# BPC_Clock.net
KiCad netlist of a schematic drawn in Altium Designer
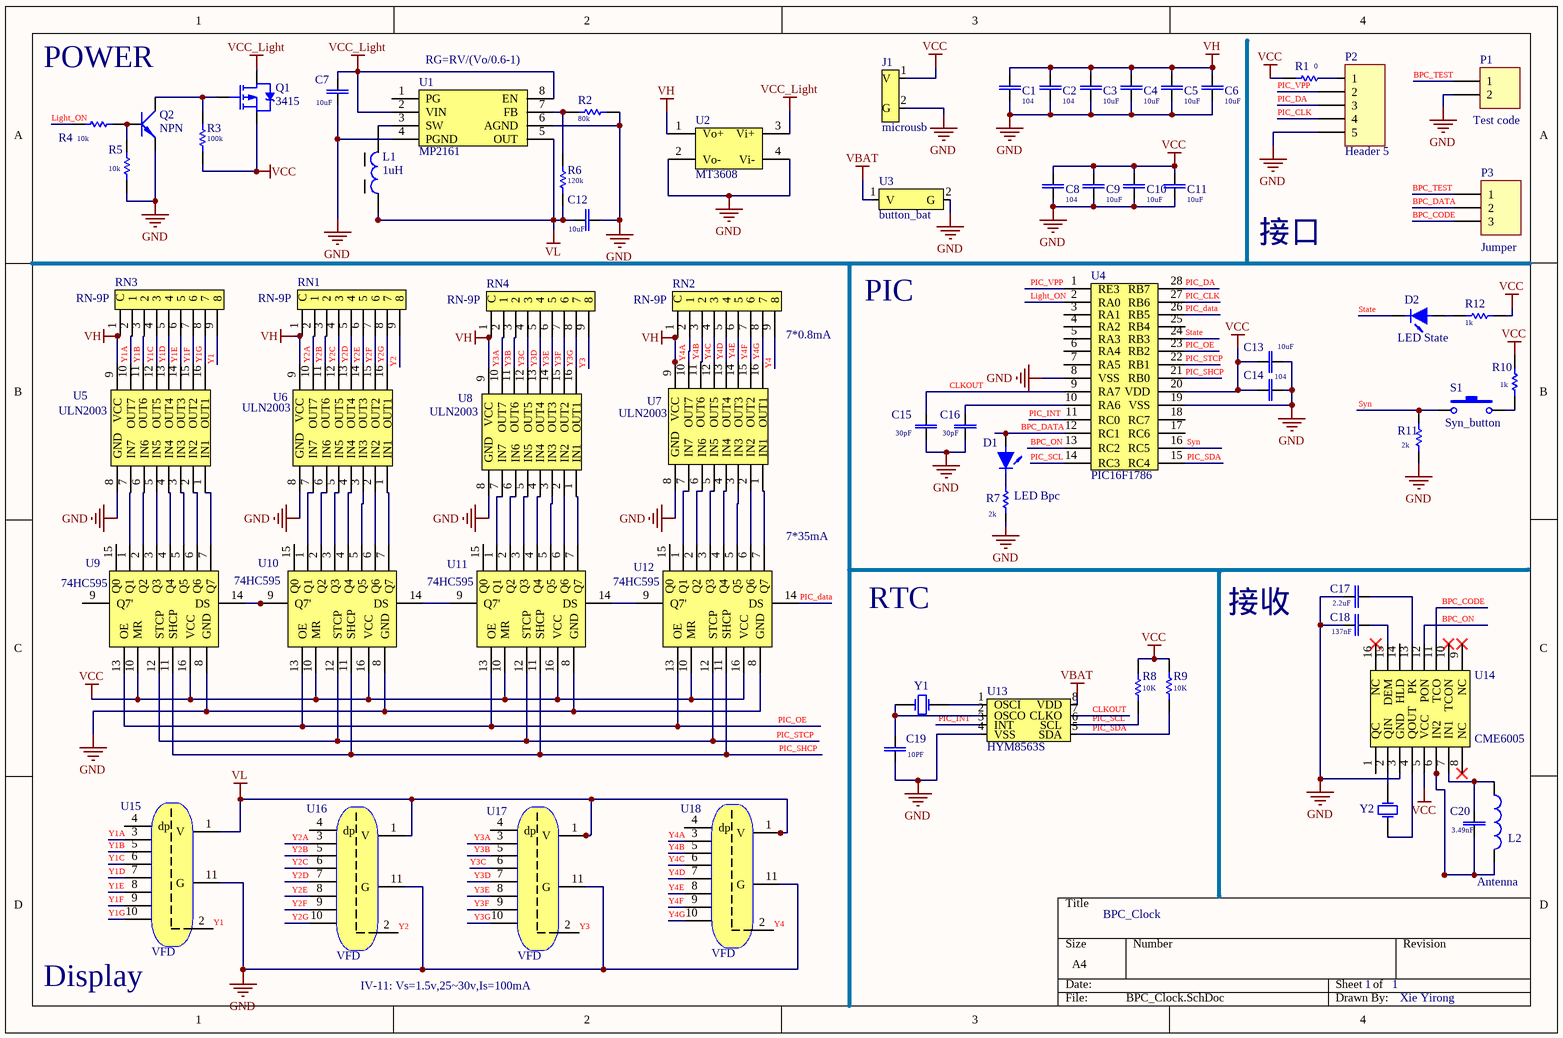
[diagram p0: BPC_Clock.SchDoc]

(export (version "E")
  (design (tool "Eeschema 10.0.6"))
  (components
    (comp (ref "C1")
      (value "104")
      (footprint "CAPC2012N")
      (description "Capacitor")
      (fields (field (name "Comment") "Cap") (field (name "PUBLISHER") "Altium Limited"))
      (libsource (lib "Miscellaneous Devices") (part "Cap"))
    )
    (comp (ref "C2")
      (value "104")
      (footprint "CAPC2012N")
      (description "Capacitor")
      (fields (field (name "Comment") "Cap") (field (name "PUBLISHER") "Altium Limited"))
      (libsource (lib "Miscellaneous Devices") (part "Cap"))
    )
    (comp (ref "C3")
      (value "10uF")
      (footprint "CAPC2012N")
      (description "Capacitor")
      (fields (field (name "Comment") "Cap") (field (name "PUBLISHER") "Altium Limited"))
      (libsource (lib "Miscellaneous Devices") (part "Cap"))
    )
    (comp (ref "C4")
      (value "10uF")
      (footprint "CAPC2012N")
      (description "Capacitor")
      (fields (field (name "Comment") "Cap") (field (name "PUBLISHER") "Altium Limited"))
      (libsource (lib "Miscellaneous Devices") (part "Cap"))
    )
    (comp (ref "C5")
      (value "10uF")
      (footprint "CAPC2012N")
      (description "Capacitor")
      (fields (field (name "Comment") "Cap") (field (name "PUBLISHER") "Altium Limited"))
      (libsource (lib "Miscellaneous Devices") (part "Cap"))
    )
    (comp (ref "C6")
      (value "10uF")
      (footprint "CAPC2012N")
      (description "Capacitor")
      (fields (field (name "Comment") "Cap") (field (name "PUBLISHER") "Altium Limited"))
      (libsource (lib "Miscellaneous Devices") (part "Cap"))
    )
    (comp (ref "C7")
      (value "10uF")
      (footprint "CAPC2012N")
      (description "Capacitor")
      (fields (field (name "Comment") "Cap") (field (name "PUBLISHER") "Altium Limited"))
      (libsource (lib "Miscellaneous Devices") (part "Cap"))
    )
    (comp (ref "C8")
      (value "104")
      (footprint "CAPC2012N")
      (description "Capacitor")
      (fields (field (name "Comment") "Cap") (field (name "PUBLISHER") "Altium Limited"))
      (libsource (lib "Miscellaneous Devices") (part "Cap"))
    )
    (comp (ref "C9")
      (value "10uF")
      (footprint "CAPC2012N")
      (description "Capacitor")
      (fields (field (name "Comment") "Cap") (field (name "PUBLISHER") "Altium Limited"))
      (libsource (lib "Miscellaneous Devices") (part "Cap"))
    )
    (comp (ref "C10")
      (value "10uF")
      (footprint "CAPC2012N")
      (description "Capacitor")
      (fields (field (name "Comment") "Cap") (field (name "PUBLISHER") "Altium Limited"))
      (libsource (lib "Miscellaneous Devices") (part "Cap"))
    )
    (comp (ref "C11")
      (value "10uF")
      (footprint "CAPC2012N")
      (description "Capacitor")
      (fields (field (name "Comment") "Cap") (field (name "PUBLISHER") "Altium Limited"))
      (libsource (lib "Miscellaneous Devices") (part "Cap"))
    )
    (comp (ref "C12")
      (value "10uF")
      (footprint "CAPC2012N")
      (description "Capacitor")
      (fields (field (name "Comment") "Cap") (field (name "PUBLISHER") "Altium Limited"))
      (libsource (lib "Miscellaneous Devices") (part "Cap"))
    )
    (comp (ref "C13")
      (value "10uF")
      (footprint "CAPC2012N")
      (description "Capacitor")
      (fields (field (name "Comment") "Cap") (field (name "PUBLISHER") "Altium Limited"))
      (libsource (lib "Miscellaneous Devices") (part "Cap"))
    )
    (comp (ref "C14")
      (value "104")
      (footprint "CAPC2012N")
      (description "Capacitor")
      (fields (field (name "Comment") "Cap") (field (name "PUBLISHER") "Altium Limited"))
      (libsource (lib "Miscellaneous Devices") (part "Cap"))
    )
    (comp (ref "C15")
      (value "30pF")
      (footprint "CAPC2012N")
      (description "Capacitor")
      (fields (field (name "Comment") "Cap") (field (name "PUBLISHER") "Altium Limited"))
      (libsource (lib "Miscellaneous Devices") (part "Cap"))
    )
    (comp (ref "C16")
      (value "30pF")
      (footprint "CAPC2012N")
      (description "Capacitor")
      (fields (field (name "Comment") "Cap") (field (name "PUBLISHER") "Altium Limited"))
      (libsource (lib "Miscellaneous Devices") (part "Cap"))
    )
    (comp (ref "C17")
      (value "2.2uF")
      (footprint "CAPC2012N")
      (description "Capacitor")
      (fields (field (name "Comment") "Cap") (field (name "PUBLISHER") "Altium Limited"))
      (libsource (lib "Miscellaneous Devices") (part "Cap"))
    )
    (comp (ref "C18")
      (value "137nF")
      (footprint "CAPC2012N")
      (description "Capacitor")
      (fields (field (name "Comment") "Cap") (field (name "PUBLISHER") "Altium Limited"))
      (libsource (lib "Miscellaneous Devices") (part "Cap"))
    )
    (comp (ref "C19")
      (value "10PF")
      (footprint "CAPC2012N")
      (description "Capacitor")
      (fields (field (name "Comment") "Cap") (field (name "PUBLISHER") "Altium Limited"))
      (libsource (lib "Miscellaneous Devices") (part "Cap"))
    )
    (comp (ref "C20")
      (value "3.49nF")
      (footprint "CAPC2012N")
      (description "Capacitor")
      (fields (field (name "Comment") "Cap") (field (name "PUBLISHER") "Altium Limited"))
      (libsource (lib "Miscellaneous Devices") (part "Cap"))
    )
    (comp (ref "D1")
      (value "LED Bpc")
      (footprint "CAPC2512N")
      (description "Typical RED, GREEN, YELLOW, AMBER GaAs LED")
      (fields (field (name "PUBLISHER") "Altium Limited"))
      (libsource (lib "Miscellaneous Devices") (part "LED2"))
    )
    (comp (ref "D2")
      (value "LED State")
      (footprint "CAPC2512N")
      (description "Typical RED, GREEN, YELLOW, AMBER GaAs LED")
      (fields (field (name "PUBLISHER") "Altium Limited"))
      (libsource (lib "Miscellaneous Devices") (part "LED2"))
    )
    (comp (ref "J1") (value "microusb") (footprint "microusb") (libsource (lib "microusb") (part "microusb")))
    (comp (ref "L1")
      (value "Chip inductors")
      (footprint "PCBComponent_1")
      (fields (field (name "ALTIUM_UNNAMED_1") "1uH"))
      (libsource (lib "Chip inductors") (part "Chip inductors"))
    )
    (comp (ref "L2")
      (value "Antenna")
      (footprint "CAPC2012N")
      (description "Inductor")
      (fields (field (name "PUBLISHER") "Altium Limited"))
      (libsource (lib "Miscellaneous Devices") (part "Inductor"))
    )
    (comp (ref "P1")
      (value "Test code")
      (footprint "HDR1X2")
      (description "Header, 2-Pin")
      (fields (field (name "PUBLISHER") "Altium Limited"))
      (libsource (lib "Miscellaneous Connectors") (part "Header 2"))
    )
    (comp (ref "P2")
      (value "Header 5")
      (footprint "HDR1X5")
      (description "Header, 5-Pin")
      (fields (field (name "PUBLISHER") "Altium Limited"))
      (libsource (lib "Miscellaneous Connectors") (part "Header 5"))
    )
    (comp (ref "P3")
      (value "Jumper")
      (footprint "HDR1X3")
      (description "Header, 3-Pin")
      (fields (field (name "PUBLISHER") "Altium Limited"))
      (libsource (lib "Miscellaneous Connectors") (part "Header 3"))
    )
    (comp (ref "Q1")
      (value "3415")
      (footprint "LC-SOT-23(SOT-23-3)")
      (description "P-Channel Power MOSFET")
      (fields (field (name "PUBLISHER") "Altium Limited"))
      (libsource (lib "Miscellaneous Devices") (part "PMOS-2"))
    )
    (comp (ref "Q2")
      (value "NPN")
      (footprint "BCY-W3")
      (description "NPN Bipolar Transistor")
      (fields (field (name "PUBLISHER") "Altium Limited"))
      (libsource (lib "Miscellaneous Devices") (part "NPN"))
    )
    (comp (ref "R1")
      (value "0")
      (footprint "RES 0805N (2012)")
      (description "Resistor")
      (fields (field (name "PUBLISHER") "Altium Limited"))
      (libsource (lib "Miscellaneous Devices") (part "Res1"))
    )
    (comp (ref "R2")
      (value "80k")
      (footprint "RES 0805N (2012)")
      (description "Resistor")
      (fields (field (name "PUBLISHER") "Altium Limited"))
      (libsource (lib "Miscellaneous Devices") (part "Res1"))
    )
    (comp (ref "R3")
      (value "100k")
      (footprint "RES 0805N (2012)")
      (description "Resistor")
      (fields (field (name "PUBLISHER") "Altium Limited"))
      (libsource (lib "Miscellaneous Devices") (part "Res1"))
    )
    (comp (ref "R4")
      (value "10k")
      (footprint "RES 0805N (2012)")
      (description "Resistor")
      (fields (field (name "PUBLISHER") "Altium Limited"))
      (libsource (lib "Miscellaneous Devices") (part "Res1"))
    )
    (comp (ref "R5")
      (value "10k")
      (footprint "RES 0805N (2012)")
      (description "Resistor")
      (fields (field (name "PUBLISHER") "Altium Limited"))
      (libsource (lib "Miscellaneous Devices") (part "Res1"))
    )
    (comp (ref "R6")
      (value "120k")
      (footprint "RES 0805N (2012)")
      (description "Resistor")
      (fields (field (name "PUBLISHER") "Altium Limited"))
      (libsource (lib "Miscellaneous Devices") (part "Res1"))
    )
    (comp (ref "R7")
      (value "2k")
      (footprint "RES 0805N (2012)")
      (description "Resistor")
      (fields (field (name "PUBLISHER") "Altium Limited"))
      (libsource (lib "Miscellaneous Devices") (part "Res1"))
    )
    (comp (ref "R8")
      (value "10K")
      (footprint "RES 0805N (2012)")
      (description "Resistor")
      (fields (field (name "PUBLISHER") "Altium Limited"))
      (libsource (lib "Miscellaneous Devices") (part "Res1"))
    )
    (comp (ref "R9")
      (value "10K")
      (footprint "RES 0805N (2012)")
      (description "Resistor")
      (fields (field (name "PUBLISHER") "Altium Limited"))
      (libsource (lib "Miscellaneous Devices") (part "Res1"))
    )
    (comp (ref "R10")
      (value "1k")
      (footprint "RES 0805N (2012)")
      (description "Resistor")
      (fields (field (name "PUBLISHER") "Altium Limited"))
      (libsource (lib "Miscellaneous Devices") (part "Res1"))
    )
    (comp (ref "R11")
      (value "2k")
      (footprint "RES 0805N (2012)")
      (description "Resistor")
      (fields (field (name "PUBLISHER") "Altium Limited"))
      (libsource (lib "Miscellaneous Devices") (part "Res1"))
    )
    (comp (ref "R12")
      (value "1k")
      (footprint "RES 0805N (2012)")
      (description "Resistor")
      (fields (field (name "PUBLISHER") "Altium Limited"))
      (libsource (lib "Miscellaneous Devices") (part "Res1"))
    )
    (comp (ref "RN1") (value "RN-9P") (footprint "RN-9P") (libsource (lib "RN-9P") (part "RN-9P")))
    (comp (ref "RN2") (value "RN-9P") (footprint "RN-9P") (libsource (lib "RN-9P") (part "RN-9P")))
    (comp (ref "RN3") (value "RN-9P") (footprint "RN-9P") (libsource (lib "RN-9P") (part "RN-9P")))
    (comp (ref "RN4") (value "RN-9P") (footprint "RN-9P") (libsource (lib "RN-9P") (part "RN-9P")))
    (comp (ref "S1")
      (value "Syn_button")
      (footprint "sw")
      (description "Switch")
      (fields (field (name "PUBLISHER") "Altium Limited"))
      (libsource (lib "Miscellaneous Devices") (part "SW-PB"))
    )
    (comp (ref "U1") (value "MP2161") (footprint "LC-TSOT-23-8") (libsource (lib "MP2161") (part "MP2161")))
    (comp (ref "U2") (value "MT3608") (footprint "MT3608") (libsource (lib "MT3608") (part "MT3608")))
    (comp (ref "U3")
      (value "button_bat")
      (footprint "button_bat")
      (libsource (lib "button_bat") (part "button_bat"))
    )
    (comp (ref "U4")
      (value "PIC16F1786")
      (footprint "PIC-28")
      (libsource (lib "PIC16F1786") (part "PIC16F1786"))
    )
    (comp (ref "U5")
      (value "ULN2003")
      (footprint "LC-SOP-16_150mil")
      (libsource (lib "ULN2003") (part "ULN2003"))
    )
    (comp (ref "U6")
      (value "ULN2003")
      (footprint "LC-SOP-16_150mil")
      (libsource (lib "ULN2003") (part "ULN2003"))
    )
    (comp (ref "U7")
      (value "ULN2003")
      (footprint "LC-SOP-16_150mil")
      (libsource (lib "ULN2003") (part "ULN2003"))
    )
    (comp (ref "U8")
      (value "ULN2003")
      (footprint "LC-SOP-16_150mil")
      (libsource (lib "ULN2003") (part "ULN2003"))
    )
    (comp (ref "U9") (value "74HC595") (footprint "LC-DIP-16") (libsource (lib "74HC595") (part "74HC595")))
    (comp (ref "U10") (value "74HC595") (footprint "LC-DIP-16") (libsource (lib "74HC595") (part "74HC595")))
    (comp (ref "U11") (value "74HC595") (footprint "LC-DIP-16") (libsource (lib "74HC595") (part "74HC595")))
    (comp (ref "U12") (value "74HC595") (footprint "LC-DIP-16") (libsource (lib "74HC595") (part "74HC595")))
    (comp (ref "U13")
      (value "HYM8563S")
      (footprint "LC-MSOP-8")
      (libsource (lib "HYM8563S") (part "HYM8563S"))
    )
    (comp (ref "U14") (value "CME6005") (footprint "CME6005") (libsource (lib "CME6005") (part "CME6005")))
    (comp (ref "U15") (value "VFD") (footprint "IV-11") (libsource (lib "VFD") (part "VFD")))
    (comp (ref "U16") (value "VFD") (footprint "IV-11") (libsource (lib "VFD") (part "VFD")))
    (comp (ref "U17") (value "VFD") (footprint "IV-11") (libsource (lib "VFD") (part "VFD")))
    (comp (ref "U18") (value "VFD") (footprint "IV-11") (libsource (lib "VFD") (part "VFD")))
    (comp (ref "Y1")
      (value "XTAL")
      (footprint "Crystal")
      (description "Crystal Oscillator")
      (fields (field (name "PUBLISHER") "Altium Limited"))
      (libsource (lib "Miscellaneous Devices") (part "XTAL"))
    )
    (comp (ref "Y2")
      (value "XTAL")
      (footprint "BCY-W2/D3.1")
      (description "Crystal Oscillator")
      (fields (field (name "PUBLISHER") "Altium Limited"))
      (libsource (lib "Miscellaneous Devices") (part "XTAL"))
    )
  )
  (nets
    (net (code "1") (name "/BPC_CODE") (class "Default")
      (node (ref "P3") (pin "3") (pinfunction "3_3") (pintype "passive"))
      (node (ref "U14") (pin "11") (pinfunction "TCO_11") (pintype "passive"))
    )
    (net (code "2") (name "/BPC_DATA") (class "Default")
      (node (ref "D1") (pin "1") (pinfunction "A_1") (pintype "passive"))
      (node (ref "P3") (pin "2") (pinfunction "2_2") (pintype "passive"))
      (node (ref "U4") (pin "12") (pinfunction "RC1_12") (pintype "passive"))
    )
    (net (code "3") (name "/BPC_ON") (class "Default")
      (node (ref "U14") (pin "12") (pinfunction "PON_12") (pintype "passive"))
      (node (ref "U4") (pin "13") (pinfunction "RC2_13") (pintype "passive"))
    )
    (net (code "4") (name "/BPC_TEST") (class "Default")
      (node (ref "P1") (pin "1") (pinfunction "1_1") (pintype "passive"))
      (node (ref "P3") (pin "1") (pinfunction "1_1") (pintype "passive"))
    )
    (net (code "5") (name "/CLKOUT") (class "Default")
      (node (ref "C15") (pin "2") (pinfunction "2_2") (pintype "passive"))
      (node (ref "U13") (pin "7") (pinfunction "CLKO_7") (pintype "passive"))
      (node (ref "U4") (pin "9") (pinfunction "RA7_9") (pintype "passive"))
    )
    (net (code "6") (name "/Light_ON") (class "Default")
      (node (ref "R4") (pin "1") (pinfunction "1_1") (pintype "passive"))
      (node (ref "U4") (pin "2") (pinfunction "RA0_2") (pintype "passive"))
    )
    (net (code "7") (name "/PIC_CLK") (class "Default")
      (node (ref "P2") (pin "4") (pinfunction "4_4") (pintype "passive"))
      (node (ref "U4") (pin "27") (pinfunction "RB6_27") (pintype "passive"))
    )
    (net (code "8") (name "/PIC_DA") (class "Default")
      (node (ref "P2") (pin "3") (pinfunction "3_3") (pintype "passive"))
      (node (ref "U4") (pin "28") (pinfunction "RB7_28") (pintype "passive"))
    )
    (net (code "9") (name "/PIC_INT") (class "Default")
      (node (ref "U13") (pin "3") (pinfunction "INT_3") (pintype "passive"))
      (node (ref "U4") (pin "11") (pinfunction "RC0_11") (pintype "passive"))
    )
    (net (code "10") (name "/PIC_OE") (class "Default")
      (node (ref "U10") (pin "13") (pinfunction "OE_13") (pintype "passive"))
      (node (ref "U11") (pin "13") (pinfunction "OE_13") (pintype "passive"))
      (node (ref "U12") (pin "13") (pinfunction "OE_13") (pintype "passive"))
      (node (ref "U4") (pin "23") (pinfunction "RB2_23") (pintype "passive"))
      (node (ref "U9") (pin "13") (pinfunction "OE_13") (pintype "passive"))
    )
    (net (code "11") (name "/PIC_SCL") (class "Default")
      (node (ref "R8") (pin "1") (pinfunction "1_1") (pintype "passive"))
      (node (ref "U13") (pin "6") (pinfunction "SCL_6") (pintype "passive"))
      (node (ref "U4") (pin "14") (pinfunction "RC3_14") (pintype "passive"))
    )
    (net (code "12") (name "/PIC_SDA") (class "Default")
      (node (ref "R9") (pin "1") (pinfunction "1_1") (pintype "passive"))
      (node (ref "U13") (pin "5") (pinfunction "SDA_5") (pintype "passive"))
      (node (ref "U4") (pin "15") (pinfunction "RC4_15") (pintype "passive"))
    )
    (net (code "13") (name "/PIC_SHCP") (class "Default")
      (node (ref "U10") (pin "11") (pinfunction "SHCP_11") (pintype "passive"))
      (node (ref "U11") (pin "11") (pinfunction "SHCP_11") (pintype "passive"))
      (node (ref "U12") (pin "11") (pinfunction "SHCP_11") (pintype "passive"))
      (node (ref "U4") (pin "21") (pinfunction "RB0_21") (pintype "passive"))
      (node (ref "U9") (pin "11") (pinfunction "SHCP_11") (pintype "passive"))
    )
    (net (code "14") (name "/PIC_STCP") (class "Default")
      (node (ref "U10") (pin "12") (pinfunction "STCP_12") (pintype "passive"))
      (node (ref "U11") (pin "12") (pinfunction "STCP_12") (pintype "passive"))
      (node (ref "U12") (pin "12") (pinfunction "STCP_12") (pintype "passive"))
      (node (ref "U4") (pin "22") (pinfunction "RB1_22") (pintype "passive"))
      (node (ref "U9") (pin "12") (pinfunction "STCP_12") (pintype "passive"))
    )
    (net (code "15") (name "/PIC_VPP") (class "Default")
      (node (ref "P2") (pin "2") (pinfunction "2_2") (pintype "passive"))
      (node (ref "U4") (pin "1") (pinfunction "RE3_1") (pintype "passive"))
    )
    (net (code "16") (name "/PIC_data") (class "Default")
      (node (ref "U12") (pin "14") (pinfunction "DS_14") (pintype "passive"))
      (node (ref "U4") (pin "26") (pinfunction "RB5_26") (pintype "passive"))
    )
    (net (code "17") (name "/State") (class "Default")
      (node (ref "D2") (pin "2") (pinfunction "K_2") (pintype "passive"))
      (node (ref "U4") (pin "24") (pinfunction "RB3_24") (pintype "passive"))
    )
    (net (code "18") (name "/Syn") (class "Default")
      (node (ref "R11") (pin "2") (pinfunction "2_2") (pintype "passive"))
      (node (ref "S1") (pin "1") (pinfunction "1_1") (pintype "passive"))
      (node (ref "U4") (pin "16") (pinfunction "RC5_16") (pintype "passive"))
    )
    (net (code "19") (name "/Y1") (class "Default")
      (node (ref "RN3") (pin "9") (pinfunction "8_9") (pintype "passive"))
      (node (ref "U15") (pin "2") (pintype "passive"))
    )
    (net (code "20") (name "/Y1A") (class "Default")
      (node (ref "RN3") (pin "2") (pinfunction "1_2") (pintype "passive"))
      (node (ref "U15") (pin "3") (pinfunction "c_3") (pintype "passive"))
      (node (ref "U5") (pin "10") (pinfunction "OUT7_10") (pintype "passive"))
    )
    (net (code "21") (name "/Y1B") (class "Default")
      (node (ref "RN3") (pin "3") (pinfunction "2_3") (pintype "passive"))
      (node (ref "U15") (pin "5") (pinfunction "e_5") (pintype "passive"))
      (node (ref "U5") (pin "11") (pinfunction "OUT6_11") (pintype "passive"))
    )
    (net (code "22") (name "/Y1C") (class "Default")
      (node (ref "RN3") (pin "4") (pinfunction "3_4") (pintype "passive"))
      (node (ref "U15") (pin "6") (pinfunction "f_6") (pintype "passive"))
      (node (ref "U5") (pin "12") (pinfunction "OUT5_12") (pintype "passive"))
    )
    (net (code "23") (name "/Y1D") (class "Default")
      (node (ref "RN3") (pin "5") (pinfunction "4_5") (pintype "passive"))
      (node (ref "U15") (pin "7") (pinfunction "g_7") (pintype "passive"))
      (node (ref "U5") (pin "13") (pinfunction "OUT4_13") (pintype "passive"))
    )
    (net (code "24") (name "/Y1E") (class "Default")
      (node (ref "RN3") (pin "6") (pinfunction "5_6") (pintype "passive"))
      (node (ref "U15") (pin "8") (pinfunction "a_8") (pintype "passive"))
      (node (ref "U5") (pin "14") (pinfunction "OUT3_14") (pintype "passive"))
    )
    (net (code "25") (name "/Y1F") (class "Default")
      (node (ref "RN3") (pin "7") (pinfunction "6_7") (pintype "passive"))
      (node (ref "U15") (pin "9") (pinfunction "b_9") (pintype "passive"))
      (node (ref "U5") (pin "15") (pinfunction "OUT2_15") (pintype "passive"))
    )
    (net (code "26") (name "/Y1G") (class "Default")
      (node (ref "RN3") (pin "8") (pinfunction "7_8") (pintype "passive"))
      (node (ref "U15") (pin "10") (pinfunction "c_10") (pintype "passive"))
      (node (ref "U5") (pin "16") (pinfunction "OUT1_16") (pintype "passive"))
    )
    (net (code "27") (name "/Y2") (class "Default")
      (node (ref "RN1") (pin "9") (pinfunction "8_9") (pintype "passive"))
      (node (ref "U16") (pin "2") (pintype "passive"))
    )
    (net (code "28") (name "/Y2A") (class "Default")
      (node (ref "RN1") (pin "2") (pinfunction "1_2") (pintype "passive"))
      (node (ref "U16") (pin "3") (pinfunction "c_3") (pintype "passive"))
      (node (ref "U6") (pin "10") (pinfunction "OUT7_10") (pintype "passive"))
    )
    (net (code "29") (name "/Y2B") (class "Default")
      (node (ref "RN1") (pin "3") (pinfunction "2_3") (pintype "passive"))
      (node (ref "U16") (pin "5") (pinfunction "e_5") (pintype "passive"))
      (node (ref "U6") (pin "11") (pinfunction "OUT6_11") (pintype "passive"))
    )
    (net (code "30") (name "/Y2C") (class "Default")
      (node (ref "RN1") (pin "4") (pinfunction "3_4") (pintype "passive"))
      (node (ref "U16") (pin "6") (pinfunction "f_6") (pintype "passive"))
      (node (ref "U6") (pin "12") (pinfunction "OUT5_12") (pintype "passive"))
    )
    (net (code "31") (name "/Y2D") (class "Default")
      (node (ref "RN1") (pin "5") (pinfunction "4_5") (pintype "passive"))
      (node (ref "U16") (pin "7") (pinfunction "g_7") (pintype "passive"))
      (node (ref "U6") (pin "13") (pinfunction "OUT4_13") (pintype "passive"))
    )
    (net (code "32") (name "/Y2E") (class "Default")
      (node (ref "RN1") (pin "6") (pinfunction "5_6") (pintype "passive"))
      (node (ref "U16") (pin "8") (pinfunction "a_8") (pintype "passive"))
      (node (ref "U6") (pin "14") (pinfunction "OUT3_14") (pintype "passive"))
    )
    (net (code "33") (name "/Y2F") (class "Default")
      (node (ref "RN1") (pin "7") (pinfunction "6_7") (pintype "passive"))
      (node (ref "U16") (pin "9") (pinfunction "b_9") (pintype "passive"))
      (node (ref "U6") (pin "15") (pinfunction "OUT2_15") (pintype "passive"))
    )
    (net (code "34") (name "/Y2G") (class "Default")
      (node (ref "RN1") (pin "8") (pinfunction "7_8") (pintype "passive"))
      (node (ref "U16") (pin "10") (pinfunction "c_10") (pintype "passive"))
      (node (ref "U6") (pin "16") (pinfunction "OUT1_16") (pintype "passive"))
    )
    (net (code "35") (name "/Y3") (class "Default")
      (node (ref "RN4") (pin "9") (pinfunction "8_9") (pintype "passive"))
      (node (ref "U17") (pin "2") (pintype "passive"))
    )
    (net (code "36") (name "/Y3A") (class "Default")
      (node (ref "RN4") (pin "2") (pinfunction "1_2") (pintype "passive"))
      (node (ref "U17") (pin "3") (pinfunction "c_3") (pintype "passive"))
      (node (ref "U8") (pin "10") (pinfunction "OUT7_10") (pintype "passive"))
    )
    (net (code "37") (name "/Y3B") (class "Default")
      (node (ref "RN4") (pin "3") (pinfunction "2_3") (pintype "passive"))
      (node (ref "U17") (pin "5") (pinfunction "e_5") (pintype "passive"))
      (node (ref "U8") (pin "11") (pinfunction "OUT6_11") (pintype "passive"))
    )
    (net (code "38") (name "/Y3C") (class "Default")
      (node (ref "RN4") (pin "4") (pinfunction "3_4") (pintype "passive"))
      (node (ref "U17") (pin "6") (pinfunction "f_6") (pintype "passive"))
      (node (ref "U8") (pin "12") (pinfunction "OUT5_12") (pintype "passive"))
    )
    (net (code "39") (name "/Y3D") (class "Default")
      (node (ref "RN4") (pin "5") (pinfunction "4_5") (pintype "passive"))
      (node (ref "U17") (pin "7") (pinfunction "g_7") (pintype "passive"))
      (node (ref "U8") (pin "13") (pinfunction "OUT4_13") (pintype "passive"))
    )
    (net (code "40") (name "/Y3E") (class "Default")
      (node (ref "RN4") (pin "6") (pinfunction "5_6") (pintype "passive"))
      (node (ref "U17") (pin "8") (pinfunction "a_8") (pintype "passive"))
      (node (ref "U8") (pin "14") (pinfunction "OUT3_14") (pintype "passive"))
    )
    (net (code "41") (name "/Y3F") (class "Default")
      (node (ref "RN4") (pin "7") (pinfunction "6_7") (pintype "passive"))
      (node (ref "U17") (pin "9") (pinfunction "b_9") (pintype "passive"))
      (node (ref "U8") (pin "15") (pinfunction "OUT2_15") (pintype "passive"))
    )
    (net (code "42") (name "/Y3G") (class "Default")
      (node (ref "RN4") (pin "8") (pinfunction "7_8") (pintype "passive"))
      (node (ref "U17") (pin "10") (pinfunction "c_10") (pintype "passive"))
      (node (ref "U8") (pin "16") (pinfunction "OUT1_16") (pintype "passive"))
    )
    (net (code "43") (name "/Y4") (class "Default")
      (node (ref "RN2") (pin "9") (pinfunction "8_9") (pintype "passive"))
      (node (ref "U18") (pin "2") (pintype "passive"))
    )
    (net (code "44") (name "/Y4A") (class "Default")
      (node (ref "RN2") (pin "2") (pinfunction "1_2") (pintype "passive"))
      (node (ref "U18") (pin "3") (pinfunction "c_3") (pintype "passive"))
      (node (ref "U7") (pin "10") (pinfunction "OUT7_10") (pintype "passive"))
    )
    (net (code "45") (name "/Y4B") (class "Default")
      (node (ref "RN2") (pin "3") (pinfunction "2_3") (pintype "passive"))
      (node (ref "U18") (pin "5") (pinfunction "e_5") (pintype "passive"))
      (node (ref "U7") (pin "11") (pinfunction "OUT6_11") (pintype "passive"))
    )
    (net (code "46") (name "/Y4C") (class "Default")
      (node (ref "RN2") (pin "4") (pinfunction "3_4") (pintype "passive"))
      (node (ref "U18") (pin "6") (pinfunction "f_6") (pintype "passive"))
      (node (ref "U7") (pin "12") (pinfunction "OUT5_12") (pintype "passive"))
    )
    (net (code "47") (name "/Y4D") (class "Default")
      (node (ref "RN2") (pin "5") (pinfunction "4_5") (pintype "passive"))
      (node (ref "U18") (pin "7") (pinfunction "g_7") (pintype "passive"))
      (node (ref "U7") (pin "13") (pinfunction "OUT4_13") (pintype "passive"))
    )
    (net (code "48") (name "/Y4E") (class "Default")
      (node (ref "RN2") (pin "6") (pinfunction "5_6") (pintype "passive"))
      (node (ref "U18") (pin "8") (pinfunction "a_8") (pintype "passive"))
      (node (ref "U7") (pin "14") (pinfunction "OUT3_14") (pintype "passive"))
    )
    (net (code "49") (name "/Y4F") (class "Default")
      (node (ref "RN2") (pin "7") (pinfunction "6_7") (pintype "passive"))
      (node (ref "U18") (pin "9") (pinfunction "b_9") (pintype "passive"))
      (node (ref "U7") (pin "15") (pinfunction "OUT2_15") (pintype "passive"))
    )
    (net (code "50") (name "/Y4G") (class "Default")
      (node (ref "RN2") (pin "8") (pinfunction "7_8") (pintype "passive"))
      (node (ref "U18") (pin "10") (pinfunction "c_10") (pintype "passive"))
      (node (ref "U7") (pin "16") (pinfunction "OUT1_16") (pintype "passive"))
    )
    (net (code "51") (name "GND") (class "Default")
      (node (ref "C1") (pin "2") (pinfunction "2_2") (pintype "passive"))
      (node (ref "C10") (pin "2") (pinfunction "2_2") (pintype "passive"))
      (node (ref "C11") (pin "2") (pinfunction "2_2") (pintype "passive"))
      (node (ref "C12") (pin "2") (pinfunction "2_2") (pintype "passive"))
      (node (ref "C13") (pin "2") (pinfunction "2_2") (pintype "passive"))
      (node (ref "C14") (pin "2") (pinfunction "2_2") (pintype "passive"))
      (node (ref "C15") (pin "1") (pinfunction "1_1") (pintype "passive"))
      (node (ref "C16") (pin "1") (pinfunction "1_1") (pintype "passive"))
      (node (ref "C17") (pin "2") (pinfunction "2_2") (pintype "passive"))
      (node (ref "C18") (pin "2") (pinfunction "2_2") (pintype "passive"))
      (node (ref "C19") (pin "2") (pinfunction "2_2") (pintype "passive"))
      (node (ref "C2") (pin "2") (pinfunction "2_2") (pintype "passive"))
      (node (ref "C3") (pin "2") (pinfunction "2_2") (pintype "passive"))
      (node (ref "C4") (pin "2") (pinfunction "2_2") (pintype "passive"))
      (node (ref "C5") (pin "2") (pinfunction "2_2") (pintype "passive"))
      (node (ref "C6") (pin "2") (pinfunction "2_2") (pintype "passive"))
      (node (ref "C7") (pin "2") (pinfunction "2_2") (pintype "passive"))
      (node (ref "C8") (pin "2") (pinfunction "2_2") (pintype "passive"))
      (node (ref "C9") (pin "2") (pinfunction "2_2") (pintype "passive"))
      (node (ref "J1") (pin "2") (pinfunction "G_2") (pintype "passive"))
      (node (ref "P1") (pin "2") (pinfunction "2_2") (pintype "passive"))
      (node (ref "P2") (pin "5") (pinfunction "5_5") (pintype "passive"))
      (node (ref "Q2") (pin "3") (pinfunction "E_3") (pintype "passive"))
      (node (ref "R11") (pin "1") (pinfunction "1_1") (pintype "passive"))
      (node (ref "R2") (pin "1") (pinfunction "1_1") (pintype "passive"))
      (node (ref "R5") (pin "1") (pinfunction "1_1") (pintype "passive"))
      (node (ref "R7") (pin "1") (pinfunction "1_1") (pintype "passive"))
      (node (ref "U1") (pin "4") (pinfunction "PGND_4") (pintype "passive"))
      (node (ref "U1") (pin "6") (pinfunction "AGND_6") (pintype "passive"))
      (node (ref "U10") (pin "8") (pinfunction "GND_8") (pintype "passive"))
      (node (ref "U11") (pin "8") (pinfunction "GND_8") (pintype "passive"))
      (node (ref "U12") (pin "8") (pinfunction "GND_8") (pintype "passive"))
      (node (ref "U13") (pin "4") (pinfunction "VSS_4") (pintype "passive"))
      (node (ref "U14") (pin "3") (pinfunction "GND_3") (pintype "passive"))
      (node (ref "U15") (pin "11") (pinfunction "G_11") (pintype "passive"))
      (node (ref "U16") (pin "11") (pinfunction "G_11") (pintype "passive"))
      (node (ref "U17") (pin "11") (pinfunction "G_11") (pintype "passive"))
      (node (ref "U18") (pin "11") (pinfunction "G_11") (pintype "passive"))
      (node (ref "U2") (pin "2") (pinfunction "Vo-_2") (pintype "passive"))
      (node (ref "U2") (pin "4") (pinfunction "Vi-_4") (pintype "passive"))
      (node (ref "U3") (pin "2") (pinfunction "G_2") (pintype "passive"))
      (node (ref "U4") (pin "19") (pinfunction "VSS_19") (pintype "passive"))
      (node (ref "U4") (pin "8") (pinfunction "VSS_8") (pintype "passive"))
      (node (ref "U5") (pin "8") (pinfunction "GND_8") (pintype "passive"))
      (node (ref "U6") (pin "8") (pinfunction "GND_8") (pintype "passive"))
      (node (ref "U7") (pin "8") (pinfunction "GND_8") (pintype "passive"))
      (node (ref "U8") (pin "8") (pinfunction "GND_8") (pintype "passive"))
      (node (ref "U9") (pin "8") (pinfunction "GND_8") (pintype "passive"))
    )
    (net (code "52") (name "Net-(D1-K)") (class "Default")
      (node (ref "D1") (pin "2") (pinfunction "K_2") (pintype "passive"))
      (node (ref "R7") (pin "2") (pinfunction "2_2") (pintype "passive"))
    )
    (net (code "53") (name "Net-(D2-A)") (class "Default")
      (node (ref "D2") (pin "1") (pinfunction "A_1") (pintype "passive"))
      (node (ref "R12") (pin "1") (pinfunction "1_1") (pintype "passive"))
    )
    (net (code "54") (name "Net-(P2-Pad1)") (class "Default")
      (node (ref "P2") (pin "1") (pinfunction "1_1") (pintype "passive"))
      (node (ref "R1") (pin "1") (pinfunction "1_1") (pintype "passive"))
    )
    (net (code "55") (name "Net-(Q1-G)") (class "Default")
      (node (ref "Q1") (pin "1") (pinfunction "G_1") (pintype "passive"))
      (node (ref "Q2") (pin "1") (pinfunction "C_1") (pintype "passive"))
      (node (ref "R3") (pin "2") (pinfunction "2_2") (pintype "passive"))
    )
    (net (code "56") (name "Net-(Q2-B)") (class "Default")
      (node (ref "Q2") (pin "2") (pinfunction "B_2") (pintype "passive"))
      (node (ref "R4") (pin "2") (pinfunction "2_2") (pintype "passive"))
      (node (ref "R5") (pin "2") (pinfunction "2_2") (pintype "passive"))
    )
    (net (code "57") (name "Net-(R10-Pad1)") (class "Default")
      (node (ref "R10") (pin "1") (pinfunction "1_1") (pintype "passive"))
      (node (ref "S1") (pin "2") (pinfunction "2_2") (pintype "passive"))
    )
    (net (code "58") (name "Net-(U1-FB)") (class "Default")
      (node (ref "R2") (pin "2") (pinfunction "2_2") (pintype "passive"))
      (node (ref "R6") (pin "1") (pinfunction "1_1") (pintype "passive"))
      (node (ref "U1") (pin "7") (pinfunction "FB_7") (pintype "passive"))
    )
    (net (code "59") (name "Net-(U1-SW)") (class "Default")
      (node (ref "L1") (pin "2") (pinfunction "2_2") (pintype "passive"))
      (node (ref "U1") (pin "3") (pinfunction "SW_3") (pintype "passive"))
    )
    (net (code "60") (name "Net-(U4-RA6)") (class "Default")
      (node (ref "C16") (pin "2") (pinfunction "2_2") (pintype "passive"))
      (node (ref "U4") (pin "10") (pinfunction "RA6_10") (pintype "passive"))
    )
    (net (code "61") (name "Net-(U5-IN1)") (class "Default")
      (node (ref "U5") (pin "1") (pinfunction "IN1_1") (pintype "passive"))
      (node (ref "U9") (pin "7") (pinfunction "Q7_7") (pintype "passive"))
    )
    (net (code "62") (name "Net-(U5-IN2)") (class "Default")
      (node (ref "U5") (pin "2") (pinfunction "IN2_2") (pintype "passive"))
      (node (ref "U9") (pin "6") (pinfunction "Q6_6") (pintype "passive"))
    )
    (net (code "63") (name "Net-(U5-IN3)") (class "Default")
      (node (ref "U5") (pin "3") (pinfunction "IN3_3") (pintype "passive"))
      (node (ref "U9") (pin "5") (pinfunction "Q5_5") (pintype "passive"))
    )
    (net (code "64") (name "Net-(U5-IN4)") (class "Default")
      (node (ref "U5") (pin "4") (pinfunction "IN4_4") (pintype "passive"))
      (node (ref "U9") (pin "4") (pinfunction "Q4_4") (pintype "passive"))
    )
    (net (code "65") (name "Net-(U5-IN5)") (class "Default")
      (node (ref "U5") (pin "5") (pinfunction "IN5_5") (pintype "passive"))
      (node (ref "U9") (pin "3") (pinfunction "Q3_3") (pintype "passive"))
    )
    (net (code "66") (name "Net-(U5-IN6)") (class "Default")
      (node (ref "U5") (pin "6") (pinfunction "IN6_6") (pintype "passive"))
      (node (ref "U9") (pin "2") (pinfunction "Q2_2") (pintype "passive"))
    )
    (net (code "67") (name "Net-(U5-IN7)") (class "Default")
      (node (ref "U5") (pin "7") (pinfunction "IN7_7") (pintype "passive"))
      (node (ref "U9") (pin "1") (pinfunction "Q1_1") (pintype "passive"))
    )
    (net (code "68") (name "Net-(U10-DS)") (class "Default")
      (node (ref "U10") (pin "14") (pinfunction "DS_14") (pintype "passive"))
      (node (ref "U11") (pin "9") (pinfunction "Q7'_9") (pintype "passive"))
    )
    (net (code "69") (name "Net-(U10-Q1)") (class "Default")
      (node (ref "U10") (pin "1") (pinfunction "Q1_1") (pintype "passive"))
      (node (ref "U6") (pin "7") (pinfunction "IN7_7") (pintype "passive"))
    )
    (net (code "70") (name "Net-(U10-Q2)") (class "Default")
      (node (ref "U10") (pin "2") (pinfunction "Q2_2") (pintype "passive"))
      (node (ref "U6") (pin "6") (pinfunction "IN6_6") (pintype "passive"))
    )
    (net (code "71") (name "Net-(U10-Q3)") (class "Default")
      (node (ref "U10") (pin "3") (pinfunction "Q3_3") (pintype "passive"))
      (node (ref "U6") (pin "5") (pinfunction "IN5_5") (pintype "passive"))
    )
    (net (code "72") (name "Net-(U10-Q4)") (class "Default")
      (node (ref "U10") (pin "4") (pinfunction "Q4_4") (pintype "passive"))
      (node (ref "U6") (pin "4") (pinfunction "IN4_4") (pintype "passive"))
    )
    (net (code "73") (name "Net-(U10-Q5)") (class "Default")
      (node (ref "U10") (pin "5") (pinfunction "Q5_5") (pintype "passive"))
      (node (ref "U6") (pin "3") (pinfunction "IN3_3") (pintype "passive"))
    )
    (net (code "74") (name "Net-(U10-Q6)") (class "Default")
      (node (ref "U10") (pin "6") (pinfunction "Q6_6") (pintype "passive"))
      (node (ref "U6") (pin "2") (pinfunction "IN2_2") (pintype "passive"))
    )
    (net (code "75") (name "Net-(U10-Q7')") (class "Default")
      (node (ref "U10") (pin "9") (pinfunction "Q7'_9") (pintype "passive"))
      (node (ref "U9") (pin "14") (pinfunction "DS_14") (pintype "passive"))
    )
    (net (code "76") (name "Net-(U10-Q7)") (class "Default")
      (node (ref "U10") (pin "7") (pinfunction "Q7_7") (pintype "passive"))
      (node (ref "U6") (pin "1") (pinfunction "IN1_1") (pintype "passive"))
    )
    (net (code "77") (name "Net-(U11-DS)") (class "Default")
      (node (ref "U11") (pin "14") (pinfunction "DS_14") (pintype "passive"))
      (node (ref "U12") (pin "9") (pinfunction "Q7'_9") (pintype "passive"))
    )
    (net (code "78") (name "Net-(U11-Q1)") (class "Default")
      (node (ref "U11") (pin "1") (pinfunction "Q1_1") (pintype "passive"))
      (node (ref "U8") (pin "7") (pinfunction "IN7_7") (pintype "passive"))
    )
    (net (code "79") (name "Net-(U11-Q2)") (class "Default")
      (node (ref "U11") (pin "2") (pinfunction "Q2_2") (pintype "passive"))
      (node (ref "U8") (pin "6") (pinfunction "IN6_6") (pintype "passive"))
    )
    (net (code "80") (name "Net-(U11-Q3)") (class "Default")
      (node (ref "U11") (pin "3") (pinfunction "Q3_3") (pintype "passive"))
      (node (ref "U8") (pin "5") (pinfunction "IN5_5") (pintype "passive"))
    )
    (net (code "81") (name "Net-(U11-Q4)") (class "Default")
      (node (ref "U11") (pin "4") (pinfunction "Q4_4") (pintype "passive"))
      (node (ref "U8") (pin "4") (pinfunction "IN4_4") (pintype "passive"))
    )
    (net (code "82") (name "Net-(U11-Q5)") (class "Default")
      (node (ref "U11") (pin "5") (pinfunction "Q5_5") (pintype "passive"))
      (node (ref "U8") (pin "3") (pinfunction "IN3_3") (pintype "passive"))
    )
    (net (code "83") (name "Net-(U11-Q6)") (class "Default")
      (node (ref "U11") (pin "6") (pinfunction "Q6_6") (pintype "passive"))
      (node (ref "U8") (pin "2") (pinfunction "IN2_2") (pintype "passive"))
    )
    (net (code "84") (name "Net-(U11-Q7)") (class "Default")
      (node (ref "U11") (pin "7") (pinfunction "Q7_7") (pintype "passive"))
      (node (ref "U8") (pin "1") (pinfunction "IN1_1") (pintype "passive"))
    )
    (net (code "85") (name "Net-(U12-Q1)") (class "Default")
      (node (ref "U12") (pin "1") (pinfunction "Q1_1") (pintype "passive"))
      (node (ref "U7") (pin "7") (pinfunction "IN7_7") (pintype "passive"))
    )
    (net (code "86") (name "Net-(U12-Q2)") (class "Default")
      (node (ref "U12") (pin "2") (pinfunction "Q2_2") (pintype "passive"))
      (node (ref "U7") (pin "6") (pinfunction "IN6_6") (pintype "passive"))
    )
    (net (code "87") (name "Net-(U12-Q3)") (class "Default")
      (node (ref "U12") (pin "3") (pinfunction "Q3_3") (pintype "passive"))
      (node (ref "U7") (pin "5") (pinfunction "IN5_5") (pintype "passive"))
    )
    (net (code "88") (name "Net-(U12-Q4)") (class "Default")
      (node (ref "U12") (pin "4") (pinfunction "Q4_4") (pintype "passive"))
      (node (ref "U7") (pin "4") (pinfunction "IN4_4") (pintype "passive"))
    )
    (net (code "89") (name "Net-(U12-Q5)") (class "Default")
      (node (ref "U12") (pin "5") (pinfunction "Q5_5") (pintype "passive"))
      (node (ref "U7") (pin "3") (pinfunction "IN3_3") (pintype "passive"))
    )
    (net (code "90") (name "Net-(U12-Q6)") (class "Default")
      (node (ref "U12") (pin "6") (pinfunction "Q6_6") (pintype "passive"))
      (node (ref "U7") (pin "2") (pinfunction "IN2_2") (pintype "passive"))
    )
    (net (code "91") (name "Net-(U12-Q7)") (class "Default")
      (node (ref "U12") (pin "7") (pinfunction "Q7_7") (pintype "passive"))
      (node (ref "U7") (pin "1") (pinfunction "IN1_1") (pintype "passive"))
    )
    (net (code "92") (name "Net-(U13-OSCI)") (class "Default")
      (node (ref "U13") (pin "1") (pinfunction "OSCI_1") (pintype "passive"))
      (node (ref "Y1") (pin "1") (pinfunction "OSC1_1") (pintype "passive"))
    )
    (net (code "93") (name "Net-(U13-OSCO)") (class "Default")
      (node (ref "C19") (pin "1") (pinfunction "1_1") (pintype "passive"))
      (node (ref "U13") (pin "2") (pinfunction "OSCO_2") (pintype "passive"))
      (node (ref "Y1") (pin "2") (pinfunction "OSC2_2") (pintype "passive"))
    )
    (net (code "94") (name "Net-(U14-DEM)") (class "Default")
      (node (ref "C18") (pin "1") (pinfunction "1_1") (pintype "passive"))
      (node (ref "U14") (pin "15") (pinfunction "DEM_15") (pintype "passive"))
    )
    (net (code "95") (name "Net-(U14-IN1)") (class "Default")
      (node (ref "C20") (pin "1") (pinfunction "1_1") (pintype "passive"))
      (node (ref "L2") (pin "1") (pinfunction "1_1") (pintype "passive"))
      (node (ref "U14") (pin "7") (pinfunction "IN1_7") (pintype "passive"))
    )
    (net (code "96") (name "Net-(U14-IN2)") (class "Default")
      (node (ref "C20") (pin "2") (pinfunction "2_2") (pintype "passive"))
      (node (ref "L2") (pin "2") (pinfunction "2_2") (pintype "passive"))
      (node (ref "U14") (pin "6") (pinfunction "IN2_6") (pintype "passive"))
    )
    (net (code "97") (name "Net-(U14-PK)") (class "Default")
      (node (ref "C17") (pin "1") (pinfunction "1_1") (pintype "passive"))
      (node (ref "U14") (pin "13") (pinfunction "PK_13") (pintype "passive"))
    )
    (net (code "98") (name "Net-(U14-QIN)") (class "Default")
      (node (ref "U14") (pin "2") (pinfunction "QIN_2") (pintype "passive"))
      (node (ref "Y2") (pin "2") (pinfunction "OSC2_2") (pintype "passive"))
    )
    (net (code "99") (name "Net-(U14-QOUT)") (class "Default")
      (node (ref "U14") (pin "4") (pinfunction "QOUT_4") (pintype "passive"))
      (node (ref "Y2") (pin "1") (pinfunction "OSC1_1") (pintype "passive"))
    )
    (net (code "100") (name "VBAT") (class "Default")
      (node (ref "U13") (pin "8") (pinfunction "VDD_8") (pintype "passive"))
      (node (ref "U3") (pin "1") (pinfunction "V_1") (pintype "passive"))
    )
    (net (code "101") (name "VCC") (class "Default")
      (node (ref "C10") (pin "1") (pinfunction "1_1") (pintype "passive"))
      (node (ref "C11") (pin "1") (pinfunction "1_1") (pintype "passive"))
      (node (ref "C13") (pin "1") (pinfunction "1_1") (pintype "passive"))
      (node (ref "C14") (pin "1") (pinfunction "1_1") (pintype "passive"))
      (node (ref "C8") (pin "1") (pinfunction "1_1") (pintype "passive"))
      (node (ref "C9") (pin "1") (pinfunction "1_1") (pintype "passive"))
      (node (ref "J1") (pin "1") (pinfunction "V_1") (pintype "passive"))
      (node (ref "Q1") (pin "3") (pinfunction "S_3") (pintype "passive"))
      (node (ref "R1") (pin "2") (pinfunction "2_2") (pintype "passive"))
      (node (ref "R10") (pin "2") (pinfunction "2_2") (pintype "passive"))
      (node (ref "R12") (pin "2") (pinfunction "2_2") (pintype "passive"))
      (node (ref "R3") (pin "1") (pinfunction "1_1") (pintype "passive"))
      (node (ref "R8") (pin "2") (pinfunction "2_2") (pintype "passive"))
      (node (ref "R9") (pin "2") (pinfunction "2_2") (pintype "passive"))
      (node (ref "U10") (pin "10") (pinfunction "MR_10") (pintype "passive"))
      (node (ref "U10") (pin "16") (pinfunction "VCC_16") (pintype "passive"))
      (node (ref "U11") (pin "10") (pinfunction "MR_10") (pintype "passive"))
      (node (ref "U11") (pin "16") (pinfunction "VCC_16") (pintype "passive"))
      (node (ref "U12") (pin "10") (pinfunction "MR_10") (pintype "passive"))
      (node (ref "U12") (pin "16") (pinfunction "VCC_16") (pintype "passive"))
      (node (ref "U14") (pin "5") (pinfunction "VCC_5") (pintype "passive"))
      (node (ref "U4") (pin "20") (pinfunction "VDD_20") (pintype "passive"))
      (node (ref "U9") (pin "10") (pinfunction "MR_10") (pintype "passive"))
      (node (ref "U9") (pin "16") (pinfunction "VCC_16") (pintype "passive"))
    )
    (net (code "102") (name "VCC_Light") (class "Default")
      (node (ref "C7") (pin "1") (pinfunction "1_1") (pintype "passive"))
      (node (ref "Q1") (pin "2") (pinfunction "D_2") (pintype "passive"))
      (node (ref "U1") (pin "2") (pinfunction "VIN_2") (pintype "passive"))
      (node (ref "U1") (pin "8") (pinfunction "EN_8") (pintype "passive"))
      (node (ref "U2") (pin "3") (pinfunction "Vi+_3") (pintype "passive"))
    )
    (net (code "103") (name "VH") (class "Default")
      (node (ref "C1") (pin "1") (pinfunction "1_1") (pintype "passive"))
      (node (ref "C2") (pin "1") (pinfunction "1_1") (pintype "passive"))
      (node (ref "C3") (pin "1") (pinfunction "1_1") (pintype "passive"))
      (node (ref "C4") (pin "1") (pinfunction "1_1") (pintype "passive"))
      (node (ref "C5") (pin "1") (pinfunction "1_1") (pintype "passive"))
      (node (ref "C6") (pin "1") (pinfunction "1_1") (pintype "passive"))
      (node (ref "RN1") (pin "1") (pinfunction "C_1") (pintype "passive"))
      (node (ref "RN2") (pin "1") (pinfunction "C_1") (pintype "passive"))
      (node (ref "RN3") (pin "1") (pinfunction "C_1") (pintype "passive"))
      (node (ref "RN4") (pin "1") (pinfunction "C_1") (pintype "passive"))
      (node (ref "U2") (pin "1") (pinfunction "Vo+_1") (pintype "passive"))
      (node (ref "U5") (pin "9") (pinfunction "VCC_9") (pintype "passive"))
      (node (ref "U6") (pin "9") (pinfunction "VCC_9") (pintype "passive"))
      (node (ref "U7") (pin "9") (pinfunction "VCC_9") (pintype "passive"))
      (node (ref "U8") (pin "9") (pinfunction "VCC_9") (pintype "passive"))
    )
    (net (code "104") (name "VL") (class "Default")
      (node (ref "C12") (pin "1") (pinfunction "1_1") (pintype "passive"))
      (node (ref "L1") (pin "1") (pinfunction "1_1") (pintype "passive"))
      (node (ref "R6") (pin "2") (pinfunction "2_2") (pintype "passive"))
      (node (ref "U1") (pin "5") (pinfunction "OUT_5") (pintype "passive"))
      (node (ref "U15") (pin "1") (pinfunction "V_1") (pintype "passive"))
      (node (ref "U16") (pin "1") (pinfunction "V_1") (pintype "passive"))
      (node (ref "U17") (pin "1") (pinfunction "V_1") (pintype "passive"))
      (node (ref "U18") (pin "1") (pinfunction "V_1") (pintype "passive"))
    )
    (net (code "105") (name "unconnected-(U1-PG-Pad1)") (class "Default")
      (node (ref "U1") (pin "1") (pinfunction "PG_1") (pintype "passive"))
    )
    (net (code "106") (name "unconnected-(U4-RA1-Pad3)") (class "Default")
      (node (ref "U4") (pin "3") (pinfunction "RA1_3") (pintype "passive"))
    )
    (net (code "107") (name "unconnected-(U4-RA2-Pad4)") (class "Default")
      (node (ref "U4") (pin "4") (pinfunction "RA2_4") (pintype "passive"))
    )
    (net (code "108") (name "unconnected-(U4-RA3-Pad5)") (class "Default")
      (node (ref "U4") (pin "5") (pinfunction "RA3_5") (pintype "passive"))
    )
    (net (code "109") (name "unconnected-(U4-RA4-Pad6)") (class "Default")
      (node (ref "U4") (pin "6") (pinfunction "RA4_6") (pintype "passive"))
    )
    (net (code "110") (name "unconnected-(U4-RA5-Pad7)") (class "Default")
      (node (ref "U4") (pin "7") (pinfunction "RA5_7") (pintype "passive"))
    )
    (net (code "111") (name "unconnected-(U4-RB4-Pad25)") (class "Default")
      (node (ref "U4") (pin "25") (pinfunction "RB4_25") (pintype "passive"))
    )
    (net (code "112") (name "unconnected-(U4-RC6-Pad17)") (class "Default")
      (node (ref "U4") (pin "17") (pinfunction "RC6_17") (pintype "passive"))
    )
    (net (code "113") (name "unconnected-(U4-RC7-Pad18)") (class "Default")
      (node (ref "U4") (pin "18") (pinfunction "RC7_18") (pintype "passive"))
    )
    (net (code "114") (name "unconnected-(U9-Q0-Pad15)") (class "Default")
      (node (ref "U9") (pin "15") (pinfunction "Q0_15") (pintype "passive"))
    )
    (net (code "115") (name "unconnected-(U9-Q7'-Pad9)") (class "Default")
      (node (ref "U9") (pin "9") (pinfunction "Q7'_9") (pintype "passive"))
    )
    (net (code "116") (name "unconnected-(U10-Q0-Pad15)") (class "Default")
      (node (ref "U10") (pin "15") (pinfunction "Q0_15") (pintype "passive"))
    )
    (net (code "117") (name "unconnected-(U11-Q0-Pad15)") (class "Default")
      (node (ref "U11") (pin "15") (pinfunction "Q0_15") (pintype "passive"))
    )
    (net (code "118") (name "unconnected-(U12-Q0-Pad15)") (class "Default")
      (node (ref "U12") (pin "15") (pinfunction "Q0_15") (pintype "passive"))
    )
    (net (code "119") (name "unconnected-(U14-HLD-Pad14)") (class "Default")
      (node (ref "U14") (pin "14") (pinfunction "HLD_14") (pintype "passive"))
    )
    (net (code "120") (name "unconnected-(U14-NC-Pad8)") (class "Default")
      (node (ref "U14") (pin "8") (pinfunction "NC_8") (pintype "passive+no_connect"))
    )
    (net (code "121") (name "unconnected-(U14-NC-Pad9)") (class "Default")
      (node (ref "U14") (pin "9") (pinfunction "NC_9") (pintype "passive+no_connect"))
    )
    (net (code "122") (name "unconnected-(U14-NC-Pad16)") (class "Default")
      (node (ref "U14") (pin "16") (pinfunction "NC_16") (pintype "passive+no_connect"))
    )
    (net (code "123") (name "unconnected-(U14-QC-Pad1)") (class "Default")
      (node (ref "U14") (pin "1") (pinfunction "QC_1") (pintype "passive"))
    )
    (net (code "124") (name "unconnected-(U14-TCON-Pad10)") (class "Default")
      (node (ref "U14") (pin "10") (pinfunction "TCON_10") (pintype "passive+no_connect"))
    )
    (net (code "125") (name "unconnected-(U15-dp-Pad4)") (class "Default")
      (node (ref "U15") (pin "4") (pinfunction "dp_4") (pintype "passive"))
    )
    (net (code "126") (name "unconnected-(U16-dp-Pad4)") (class "Default")
      (node (ref "U16") (pin "4") (pinfunction "dp_4") (pintype "passive"))
    )
    (net (code "127") (name "unconnected-(U17-dp-Pad4)") (class "Default")
      (node (ref "U17") (pin "4") (pinfunction "dp_4") (pintype "passive"))
    )
    (net (code "128") (name "unconnected-(U18-dp-Pad4)") (class "Default")
      (node (ref "U18") (pin "4") (pinfunction "dp_4") (pintype "passive"))
    )
  )
)
